# minimoog-filter.net
KiCad netlist of a schematic drawn in EAGLE
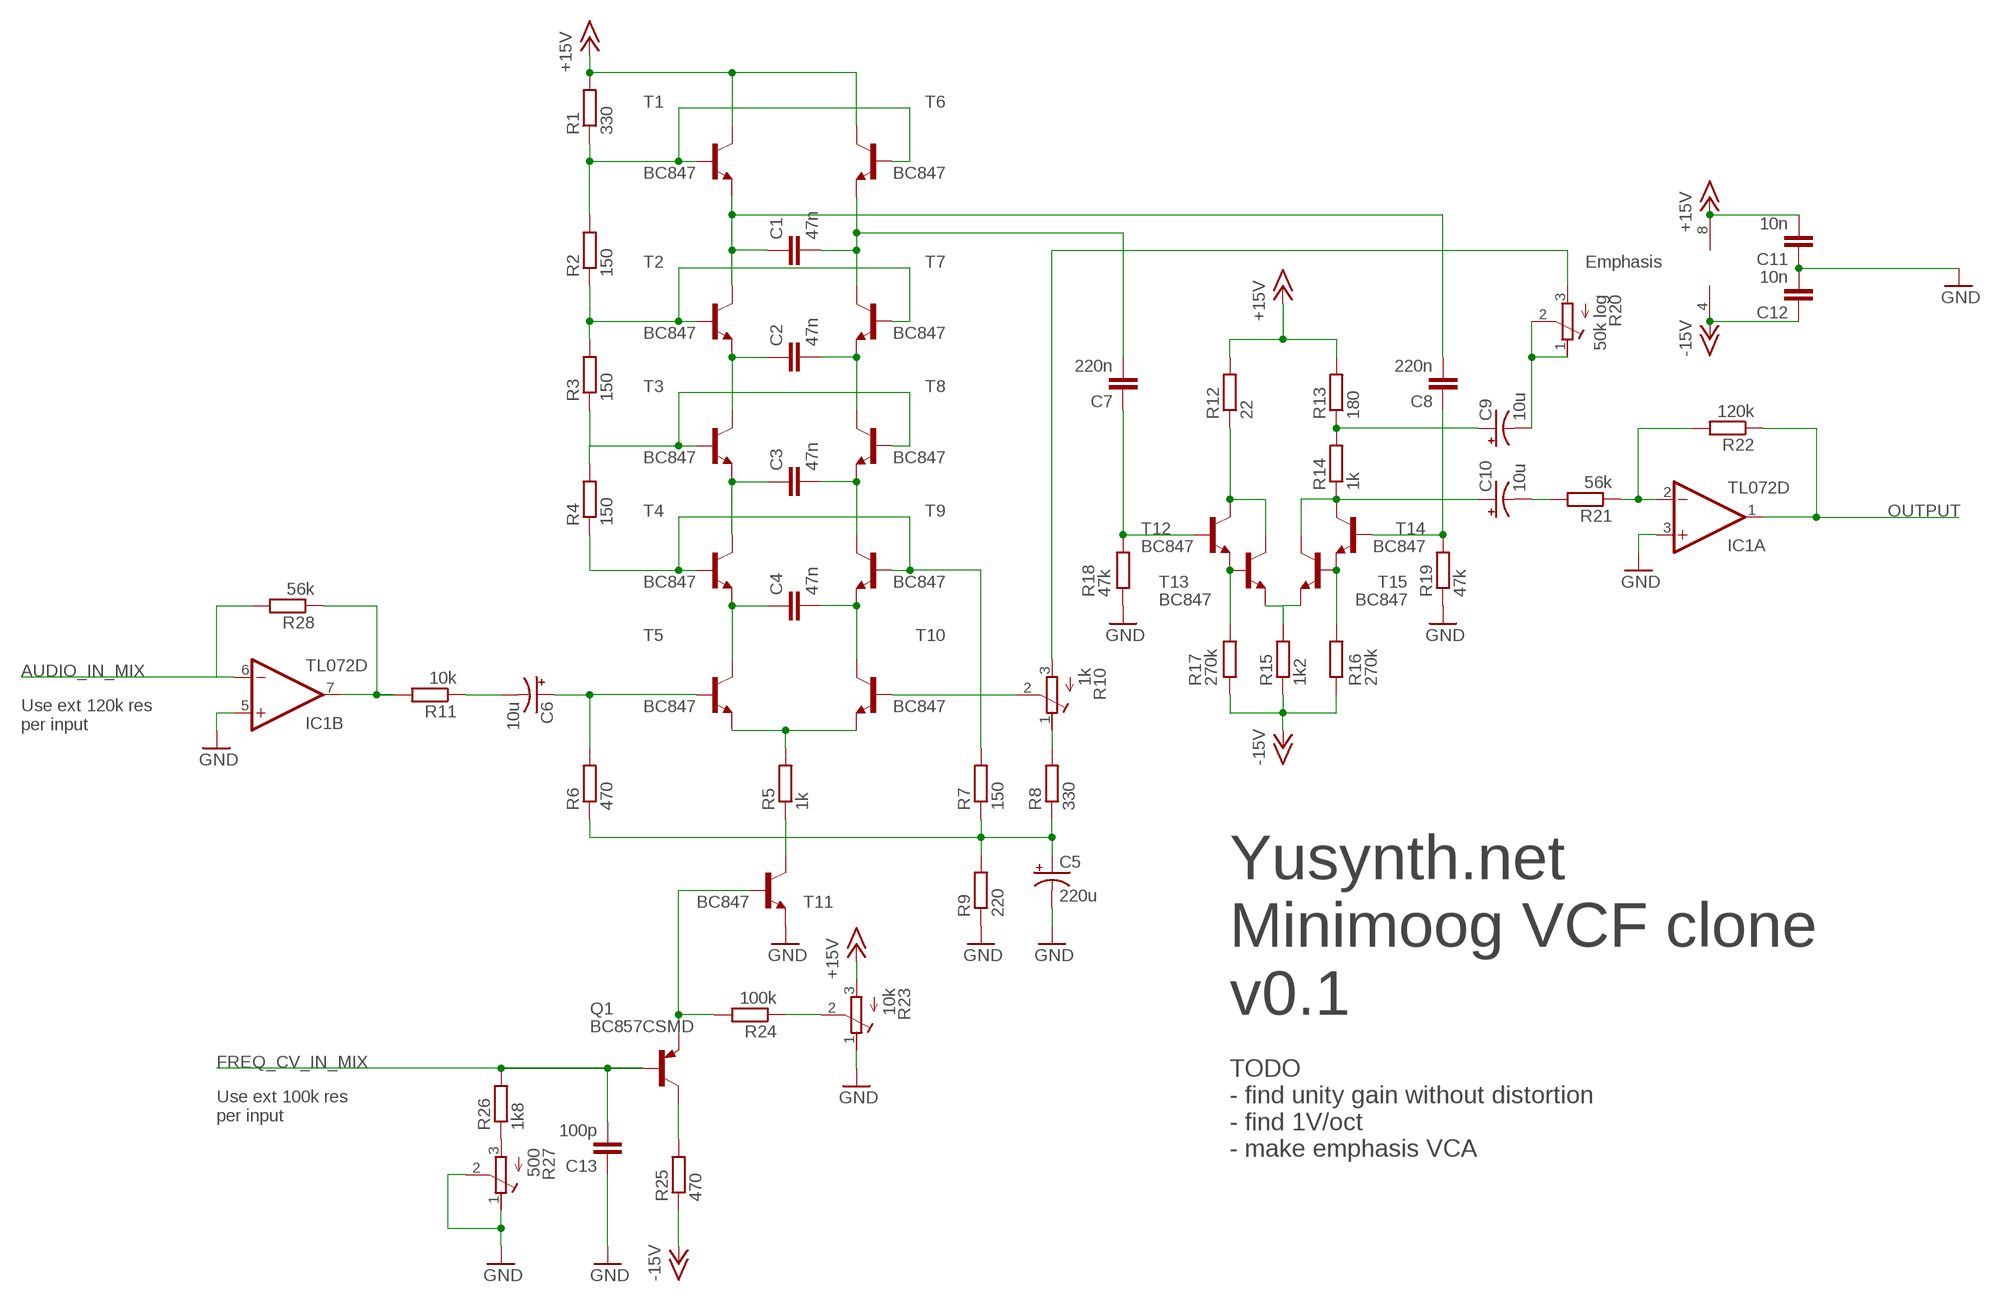
[diagram p0: schematic, sheet 1]

(export (version "E")
  (design (tool "Eeschema 10.0.6"))
  (components
    (comp (ref "C1")
      (value "47n")
      (footprint "eagle-import:C0805")
      (libsource (lib "eagle-import") (part "C-EUC0805"))
    )
    (comp (ref "C2")
      (value "47n")
      (footprint "eagle-import:C0805")
      (libsource (lib "eagle-import") (part "C-EUC0805"))
    )
    (comp (ref "C3")
      (value "47n")
      (footprint "eagle-import:C0805")
      (libsource (lib "eagle-import") (part "C-EUC0805"))
    )
    (comp (ref "C4")
      (value "47n")
      (footprint "eagle-import:C0805")
      (libsource (lib "eagle-import") (part "C-EUC0805"))
    )
    (comp (ref "C5")
      (value "220u")
      (footprint "eagle-import:E2-5")
      (libsource (lib "eagle-import") (part "CPOL-USE2-5"))
    )
    (comp (ref "C6")
      (value "10u")
      (footprint "eagle-import:E2-5")
      (libsource (lib "eagle-import") (part "CPOL-USE2-5"))
    )
    (comp (ref "C7")
      (value "220n")
      (footprint "eagle-import:C0805")
      (libsource (lib "eagle-import") (part "C-EUC0805"))
    )
    (comp (ref "C8")
      (value "220n")
      (footprint "eagle-import:C0805")
      (libsource (lib "eagle-import") (part "C-EUC0805"))
    )
    (comp (ref "C9")
      (value "10u")
      (footprint "eagle-import:E2-5")
      (libsource (lib "eagle-import") (part "CPOL-USE2-5"))
    )
    (comp (ref "C10")
      (value "10u")
      (footprint "eagle-import:E2-5")
      (libsource (lib "eagle-import") (part "CPOL-USE2-5"))
    )
    (comp (ref "C11")
      (value "10n")
      (footprint "eagle-import:C0805")
      (libsource (lib "eagle-import") (part "C-EUC0805"))
    )
    (comp (ref "C12")
      (value "10n")
      (footprint "eagle-import:C0805")
      (libsource (lib "eagle-import") (part "C-EUC0805"))
    )
    (comp (ref "C13")
      (value "100p")
      (footprint "eagle-import:C0805")
      (libsource (lib "eagle-import") (part "C-EUC0805"))
    )
    (comp (ref "IC1")
      (value "TL072D")
      (footprint "eagle-import:SO08")
      (libsource (lib "eagle-import") (part "TL072D"))
    )
    (comp (ref "Q1")
      (value "BC857CSMD")
      (footprint "eagle-import:SOT23-BEC")
      (libsource (lib "eagle-import") (part "BC857SMDC"))
    )
    (comp (ref "R1")
      (value "330")
      (footprint "eagle-import:R0805")
      (libsource (lib "eagle-import") (part "R-EU_R0805"))
    )
    (comp (ref "R2")
      (value "150")
      (footprint "eagle-import:R0805")
      (libsource (lib "eagle-import") (part "R-EU_R0805"))
    )
    (comp (ref "R3")
      (value "150")
      (footprint "eagle-import:R0805")
      (libsource (lib "eagle-import") (part "R-EU_R0805"))
    )
    (comp (ref "R4")
      (value "150")
      (footprint "eagle-import:R0805")
      (libsource (lib "eagle-import") (part "R-EU_R0805"))
    )
    (comp (ref "R5")
      (value "1k")
      (footprint "eagle-import:R0805")
      (libsource (lib "eagle-import") (part "R-EU_R0805"))
    )
    (comp (ref "R6")
      (value "470")
      (footprint "eagle-import:R0805")
      (libsource (lib "eagle-import") (part "R-EU_R0805"))
    )
    (comp (ref "R7")
      (value "150")
      (footprint "eagle-import:R0805")
      (libsource (lib "eagle-import") (part "R-EU_R0805"))
    )
    (comp (ref "R8")
      (value "330")
      (footprint "eagle-import:R0805")
      (libsource (lib "eagle-import") (part "R-EU_R0805"))
    )
    (comp (ref "R9")
      (value "220")
      (footprint "eagle-import:R0805")
      (libsource (lib "eagle-import") (part "R-EU_R0805"))
    )
    (comp (ref "R10")
      (value "1k")
      (footprint "eagle-import:RTRIMT93YA")
      (libsource (lib "eagle-import") (part "R-TRIMMT93YA"))
    )
    (comp (ref "R11")
      (value "10k")
      (footprint "eagle-import:R0805")
      (libsource (lib "eagle-import") (part "R-EU_R0805"))
    )
    (comp (ref "R12")
      (value "22")
      (footprint "eagle-import:R0805")
      (libsource (lib "eagle-import") (part "R-EU_R0805"))
    )
    (comp (ref "R13")
      (value "180")
      (footprint "eagle-import:R0805")
      (libsource (lib "eagle-import") (part "R-EU_R0805"))
    )
    (comp (ref "R14")
      (value "1k")
      (footprint "eagle-import:R0805")
      (libsource (lib "eagle-import") (part "R-EU_R0805"))
    )
    (comp (ref "R15")
      (value "1k2")
      (footprint "eagle-import:R0805")
      (libsource (lib "eagle-import") (part "R-EU_R0805"))
    )
    (comp (ref "R16")
      (value "270k")
      (footprint "eagle-import:R0805")
      (libsource (lib "eagle-import") (part "R-EU_R0805"))
    )
    (comp (ref "R17")
      (value "270k")
      (footprint "eagle-import:R0805")
      (libsource (lib "eagle-import") (part "R-EU_R0805"))
    )
    (comp (ref "R18")
      (value "47k")
      (footprint "eagle-import:R0805")
      (libsource (lib "eagle-import") (part "R-EU_R0805"))
    )
    (comp (ref "R19")
      (value "47k")
      (footprint "eagle-import:R0805")
      (libsource (lib "eagle-import") (part "R-EU_R0805"))
    )
    (comp (ref "R20")
      (value "50k log")
      (footprint "eagle-import:RTRIMT93YA")
      (libsource (lib "eagle-import") (part "R-TRIMMT93YA"))
    )
    (comp (ref "R21")
      (value "56k")
      (footprint "eagle-import:R0805")
      (libsource (lib "eagle-import") (part "R-EU_R0805"))
    )
    (comp (ref "R22")
      (value "120k")
      (footprint "eagle-import:R0805")
      (libsource (lib "eagle-import") (part "R-EU_R0805"))
    )
    (comp (ref "R23")
      (value "10k")
      (footprint "eagle-import:RTRIMT93YA")
      (libsource (lib "eagle-import") (part "R-TRIMMT93YA"))
    )
    (comp (ref "R24")
      (value "100k")
      (footprint "eagle-import:R0805")
      (libsource (lib "eagle-import") (part "R-EU_R0805"))
    )
    (comp (ref "R25")
      (value "470")
      (footprint "eagle-import:R0805")
      (libsource (lib "eagle-import") (part "R-EU_R0805"))
    )
    (comp (ref "R26")
      (value "1k8")
      (footprint "eagle-import:R0805")
      (libsource (lib "eagle-import") (part "R-EU_R0805"))
    )
    (comp (ref "R27")
      (value "500")
      (footprint "eagle-import:RTRIMT93YA")
      (libsource (lib "eagle-import") (part "R-TRIMMT93YA"))
    )
    (comp (ref "R28")
      (value "56k")
      (footprint "eagle-import:R0805")
      (libsource (lib "eagle-import") (part "R-EU_R0805"))
    )
    (comp (ref "T1")
      (value "BC847")
      (footprint "eagle-import:SOT23")
      (libsource (lib "eagle-import") (part "BC847"))
    )
    (comp (ref "T2")
      (value "BC847")
      (footprint "eagle-import:SOT23")
      (libsource (lib "eagle-import") (part "BC847"))
    )
    (comp (ref "T3")
      (value "BC847")
      (footprint "eagle-import:SOT23")
      (libsource (lib "eagle-import") (part "BC847"))
    )
    (comp (ref "T4")
      (value "BC847")
      (footprint "eagle-import:SOT23")
      (libsource (lib "eagle-import") (part "BC847"))
    )
    (comp (ref "T5")
      (value "BC847")
      (footprint "eagle-import:SOT23")
      (libsource (lib "eagle-import") (part "BC847"))
    )
    (comp (ref "T6")
      (value "BC847")
      (footprint "eagle-import:SOT23")
      (libsource (lib "eagle-import") (part "BC847"))
    )
    (comp (ref "T7")
      (value "BC847")
      (footprint "eagle-import:SOT23")
      (libsource (lib "eagle-import") (part "BC847"))
    )
    (comp (ref "T8")
      (value "BC847")
      (footprint "eagle-import:SOT23")
      (libsource (lib "eagle-import") (part "BC847"))
    )
    (comp (ref "T9")
      (value "BC847")
      (footprint "eagle-import:SOT23")
      (libsource (lib "eagle-import") (part "BC847"))
    )
    (comp (ref "T10")
      (value "BC847")
      (footprint "eagle-import:SOT23")
      (libsource (lib "eagle-import") (part "BC847"))
    )
    (comp (ref "T11")
      (value "BC847")
      (footprint "eagle-import:SOT23")
      (libsource (lib "eagle-import") (part "BC847"))
    )
    (comp (ref "T12")
      (value "BC847")
      (footprint "eagle-import:SOT23")
      (libsource (lib "eagle-import") (part "BC847"))
    )
    (comp (ref "T13")
      (value "BC847")
      (footprint "eagle-import:SOT23")
      (libsource (lib "eagle-import") (part "BC847"))
    )
    (comp (ref "T14")
      (value "BC847")
      (footprint "eagle-import:SOT23")
      (libsource (lib "eagle-import") (part "BC847"))
    )
    (comp (ref "T15")
      (value "BC847")
      (footprint "eagle-import:SOT23")
      (libsource (lib "eagle-import") (part "BC847"))
    )
  )
  (nets
    (net (code "1") (name "+15V") (class "Default")
      (node (ref "C11") (pin "2") (pinfunction "2_2") (pintype "passive"))
      (node (ref "IC1") (pin "8") (pinfunction "V+_8") (pintype "power_in"))
      (node (ref "R1") (pin "2") (pinfunction "2_2") (pintype "passive"))
      (node (ref "R12") (pin "2") (pinfunction "2_2") (pintype "passive"))
      (node (ref "R13") (pin "2") (pinfunction "2_2") (pintype "passive"))
      (node (ref "R23") (pin "3") (pinfunction "E_3") (pintype "passive"))
      (node (ref "T1") (pin "3") (pinfunction "C_3") (pintype "passive"))
      (node (ref "T6") (pin "3") (pinfunction "C_3") (pintype "passive"))
    )
    (net (code "2") (name "-15V") (class "Default")
      (node (ref "C12") (pin "1") (pinfunction "1_1") (pintype "passive"))
      (node (ref "IC1") (pin "4") (pinfunction "V-_4") (pintype "power_in"))
      (node (ref "R15") (pin "1") (pinfunction "1_1") (pintype "passive"))
      (node (ref "R16") (pin "1") (pinfunction "1_1") (pintype "passive"))
      (node (ref "R17") (pin "1") (pinfunction "1_1") (pintype "passive"))
      (node (ref "R25") (pin "1") (pinfunction "1_1") (pintype "passive"))
    )
    (net (code "3") (name "/AUDIO_IN_MIX") (class "Default")
      (node (ref "IC1") (pin "6") (pinfunction "-IN_6") (pintype "input"))
      (node (ref "R28") (pin "2") (pinfunction "2_2") (pintype "passive"))
    )
    (net (code "4") (name "/FREQ_CV_IN_MIX") (class "Default")
      (node (ref "C13") (pin "2") (pinfunction "2_2") (pintype "passive"))
      (node (ref "Q1") (pin "B") (pinfunction "B_B") (pintype "passive"))
      (node (ref "R26") (pin "2") (pinfunction "2_2") (pintype "passive"))
    )
    (net (code "5") (name "/OUTPUT") (class "Default")
      (node (ref "IC1") (pin "1") (pinfunction "OUT_1") (pintype "output"))
      (node (ref "R22") (pin "1") (pinfunction "1_1") (pintype "passive"))
    )
    (net (code "6") (name "GND") (class "Default")
      (node (ref "C11") (pin "1") (pinfunction "1_1") (pintype "passive"))
      (node (ref "C12") (pin "2") (pinfunction "2_2") (pintype "passive"))
      (node (ref "C13") (pin "1") (pinfunction "1_1") (pintype "passive"))
      (node (ref "C5") (pin "-") (pinfunction "-_-") (pintype "passive"))
      (node (ref "IC1") (pin "3") (pinfunction "+IN_3") (pintype "input"))
      (node (ref "IC1") (pin "5") (pinfunction "+IN_5") (pintype "input"))
      (node (ref "R18") (pin "1") (pinfunction "1_1") (pintype "passive"))
      (node (ref "R19") (pin "1") (pinfunction "1_1") (pintype "passive"))
      (node (ref "R23") (pin "1") (pinfunction "A_1") (pintype "passive"))
      (node (ref "R27") (pin "1") (pinfunction "A_1") (pintype "passive"))
      (node (ref "R27") (pin "2") (pinfunction "S_2") (pintype "passive"))
      (node (ref "R9") (pin "1") (pinfunction "1_1") (pintype "passive"))
      (node (ref "T11") (pin "2") (pinfunction "E_2") (pintype "passive"))
    )
    (net (code "7") (name "Net-(C5-Pad+)") (class "Default")
      (node (ref "C5") (pin "+") (pinfunction "+_+") (pintype "passive"))
      (node (ref "R6") (pin "1") (pinfunction "1_1") (pintype "passive"))
      (node (ref "R7") (pin "1") (pinfunction "1_1") (pintype "passive"))
      (node (ref "R8") (pin "1") (pinfunction "1_1") (pintype "passive"))
      (node (ref "R9") (pin "2") (pinfunction "2_2") (pintype "passive"))
    )
    (net (code "8") (name "Net-(C6-Pad-)") (class "Default")
      (node (ref "C6") (pin "-") (pinfunction "-_-") (pintype "passive"))
      (node (ref "R11") (pin "1") (pinfunction "1_1") (pintype "passive"))
    )
    (net (code "9") (name "Net-(C9-Pad+)") (class "Default")
      (node (ref "C9") (pin "+") (pinfunction "+_+") (pintype "passive"))
      (node (ref "R13") (pin "1") (pinfunction "1_1") (pintype "passive"))
      (node (ref "R14") (pin "2") (pinfunction "2_2") (pintype "passive"))
    )
    (net (code "10") (name "Net-(C10-Pad-)") (class "Default")
      (node (ref "C10") (pin "-") (pinfunction "-_-") (pintype "passive"))
      (node (ref "R21") (pin "2") (pinfunction "2_2") (pintype "passive"))
    )
    (net (code "11") (name "Net-(IC1A--IN)") (class "Default")
      (node (ref "IC1") (pin "2") (pinfunction "-IN_2") (pintype "input"))
      (node (ref "R21") (pin "1") (pinfunction "1_1") (pintype "passive"))
      (node (ref "R22") (pin "2") (pinfunction "2_2") (pintype "passive"))
    )
    (net (code "12") (name "Net-(IC1B-OUT)") (class "Default")
      (node (ref "IC1") (pin "7") (pinfunction "OUT_7") (pintype "output"))
      (node (ref "R11") (pin "2") (pinfunction "2_2") (pintype "passive"))
      (node (ref "R28") (pin "1") (pinfunction "1_1") (pintype "passive"))
    )
    (net (code "13") (name "Net-(Q1-PadC)") (class "Default")
      (node (ref "Q1") (pin "C") (pinfunction "C_C") (pintype "passive"))
      (node (ref "R25") (pin "2") (pinfunction "2_2") (pintype "passive"))
    )
    (net (code "14") (name "Net-(R10-A)") (class "Default")
      (node (ref "R10") (pin "1") (pinfunction "A_1") (pintype "passive"))
      (node (ref "R8") (pin "2") (pinfunction "2_2") (pintype "passive"))
    )
    (net (code "15") (name "Net-(R10-E)") (class "Default")
      (node (ref "R10") (pin "3") (pinfunction "E_3") (pintype "passive"))
      (node (ref "R20") (pin "3") (pinfunction "E_3") (pintype "passive"))
    )
    (net (code "16") (name "Net-(R10-S)") (class "Default")
      (node (ref "R10") (pin "2") (pinfunction "S_2") (pintype "passive"))
      (node (ref "T10") (pin "1") (pinfunction "B_1") (pintype "passive"))
    )
    (net (code "17") (name "Net-(R20-A)") (class "Default")
      (node (ref "C9") (pin "-") (pinfunction "-_-") (pintype "passive"))
      (node (ref "R20") (pin "1") (pinfunction "A_1") (pintype "passive"))
      (node (ref "R20") (pin "2") (pinfunction "S_2") (pintype "passive"))
    )
    (net (code "18") (name "Net-(R23-S)") (class "Default")
      (node (ref "R23") (pin "2") (pinfunction "S_2") (pintype "passive"))
      (node (ref "R24") (pin "1") (pinfunction "1_1") (pintype "passive"))
    )
    (net (code "19") (name "Net-(R27-E)") (class "Default")
      (node (ref "R26") (pin "1") (pinfunction "1_1") (pintype "passive"))
      (node (ref "R27") (pin "3") (pinfunction "E_3") (pintype "passive"))
    )
    (net (code "20") (name "Net-(T1-B)") (class "Default")
      (node (ref "R1") (pin "1") (pinfunction "1_1") (pintype "passive"))
      (node (ref "R2") (pin "2") (pinfunction "2_2") (pintype "passive"))
      (node (ref "T1") (pin "1") (pinfunction "B_1") (pintype "passive"))
      (node (ref "T6") (pin "1") (pinfunction "B_1") (pintype "passive"))
    )
    (net (code "21") (name "Net-(T1-E)") (class "Default")
      (node (ref "C1") (pin "1") (pinfunction "1_1") (pintype "passive"))
      (node (ref "C8") (pin "2") (pinfunction "2_2") (pintype "passive"))
      (node (ref "T1") (pin "2") (pinfunction "E_2") (pintype "passive"))
      (node (ref "T2") (pin "3") (pinfunction "C_3") (pintype "passive"))
    )
    (net (code "22") (name "Net-(T2-B)") (class "Default")
      (node (ref "R2") (pin "1") (pinfunction "1_1") (pintype "passive"))
      (node (ref "R3") (pin "2") (pinfunction "2_2") (pintype "passive"))
      (node (ref "T2") (pin "1") (pinfunction "B_1") (pintype "passive"))
      (node (ref "T7") (pin "1") (pinfunction "B_1") (pintype "passive"))
    )
    (net (code "23") (name "Net-(T2-E)") (class "Default")
      (node (ref "C2") (pin "1") (pinfunction "1_1") (pintype "passive"))
      (node (ref "T2") (pin "2") (pinfunction "E_2") (pintype "passive"))
      (node (ref "T3") (pin "3") (pinfunction "C_3") (pintype "passive"))
    )
    (net (code "24") (name "Net-(T3-B)") (class "Default")
      (node (ref "R3") (pin "1") (pinfunction "1_1") (pintype "passive"))
      (node (ref "R4") (pin "2") (pinfunction "2_2") (pintype "passive"))
      (node (ref "T3") (pin "1") (pinfunction "B_1") (pintype "passive"))
      (node (ref "T8") (pin "1") (pinfunction "B_1") (pintype "passive"))
    )
    (net (code "25") (name "Net-(T3-E)") (class "Default")
      (node (ref "C3") (pin "1") (pinfunction "1_1") (pintype "passive"))
      (node (ref "T3") (pin "2") (pinfunction "E_2") (pintype "passive"))
      (node (ref "T4") (pin "3") (pinfunction "C_3") (pintype "passive"))
    )
    (net (code "26") (name "Net-(T4-B)") (class "Default")
      (node (ref "R4") (pin "1") (pinfunction "1_1") (pintype "passive"))
      (node (ref "R7") (pin "2") (pinfunction "2_2") (pintype "passive"))
      (node (ref "T4") (pin "1") (pinfunction "B_1") (pintype "passive"))
      (node (ref "T9") (pin "1") (pinfunction "B_1") (pintype "passive"))
    )
    (net (code "27") (name "Net-(T4-E)") (class "Default")
      (node (ref "C4") (pin "1") (pinfunction "1_1") (pintype "passive"))
      (node (ref "T4") (pin "2") (pinfunction "E_2") (pintype "passive"))
      (node (ref "T5") (pin "3") (pinfunction "C_3") (pintype "passive"))
    )
    (net (code "28") (name "Net-(T5-B)") (class "Default")
      (node (ref "C6") (pin "+") (pinfunction "+_+") (pintype "passive"))
      (node (ref "R6") (pin "2") (pinfunction "2_2") (pintype "passive"))
      (node (ref "T5") (pin "1") (pinfunction "B_1") (pintype "passive"))
    )
    (net (code "29") (name "Net-(T6-E)") (class "Default")
      (node (ref "C1") (pin "2") (pinfunction "2_2") (pintype "passive"))
      (node (ref "C7") (pin "2") (pinfunction "2_2") (pintype "passive"))
      (node (ref "T6") (pin "2") (pinfunction "E_2") (pintype "passive"))
      (node (ref "T7") (pin "3") (pinfunction "C_3") (pintype "passive"))
    )
    (net (code "30") (name "Net-(T7-E)") (class "Default")
      (node (ref "C2") (pin "2") (pinfunction "2_2") (pintype "passive"))
      (node (ref "T7") (pin "2") (pinfunction "E_2") (pintype "passive"))
      (node (ref "T8") (pin "3") (pinfunction "C_3") (pintype "passive"))
    )
    (net (code "31") (name "Net-(T8-E)") (class "Default")
      (node (ref "C3") (pin "2") (pinfunction "2_2") (pintype "passive"))
      (node (ref "T8") (pin "2") (pinfunction "E_2") (pintype "passive"))
      (node (ref "T9") (pin "3") (pinfunction "C_3") (pintype "passive"))
    )
    (net (code "32") (name "Net-(T10-C)") (class "Default")
      (node (ref "C4") (pin "2") (pinfunction "2_2") (pintype "passive"))
      (node (ref "T10") (pin "3") (pinfunction "C_3") (pintype "passive"))
      (node (ref "T9") (pin "2") (pinfunction "E_2") (pintype "passive"))
    )
    (net (code "33") (name "Net-(T10-E)") (class "Default")
      (node (ref "R5") (pin "2") (pinfunction "2_2") (pintype "passive"))
      (node (ref "T10") (pin "2") (pinfunction "E_2") (pintype "passive"))
      (node (ref "T5") (pin "2") (pinfunction "E_2") (pintype "passive"))
    )
    (net (code "34") (name "Net-(T11-B)") (class "Default")
      (node (ref "Q1") (pin "E") (pinfunction "E_E") (pintype "passive"))
      (node (ref "R24") (pin "2") (pinfunction "2_2") (pintype "passive"))
      (node (ref "T11") (pin "1") (pinfunction "B_1") (pintype "passive"))
    )
    (net (code "35") (name "Net-(T11-C)") (class "Default")
      (node (ref "R5") (pin "1") (pinfunction "1_1") (pintype "passive"))
      (node (ref "T11") (pin "3") (pinfunction "C_3") (pintype "passive"))
    )
    (net (code "36") (name "Net-(T12-B)") (class "Default")
      (node (ref "C7") (pin "1") (pinfunction "1_1") (pintype "passive"))
      (node (ref "R18") (pin "2") (pinfunction "2_2") (pintype "passive"))
      (node (ref "T12") (pin "1") (pinfunction "B_1") (pintype "passive"))
    )
    (net (code "37") (name "Net-(T12-C)") (class "Default")
      (node (ref "R12") (pin "1") (pinfunction "1_1") (pintype "passive"))
      (node (ref "T12") (pin "3") (pinfunction "C_3") (pintype "passive"))
      (node (ref "T13") (pin "3") (pinfunction "C_3") (pintype "passive"))
    )
    (net (code "38") (name "Net-(T12-E)") (class "Default")
      (node (ref "R17") (pin "2") (pinfunction "2_2") (pintype "passive"))
      (node (ref "T12") (pin "2") (pinfunction "E_2") (pintype "passive"))
      (node (ref "T13") (pin "1") (pinfunction "B_1") (pintype "passive"))
    )
    (net (code "39") (name "Net-(T13-E)") (class "Default")
      (node (ref "R15") (pin "2") (pinfunction "2_2") (pintype "passive"))
      (node (ref "T13") (pin "2") (pinfunction "E_2") (pintype "passive"))
      (node (ref "T15") (pin "2") (pinfunction "E_2") (pintype "passive"))
    )
    (net (code "40") (name "Net-(T14-B)") (class "Default")
      (node (ref "C8") (pin "1") (pinfunction "1_1") (pintype "passive"))
      (node (ref "R19") (pin "2") (pinfunction "2_2") (pintype "passive"))
      (node (ref "T14") (pin "1") (pinfunction "B_1") (pintype "passive"))
    )
    (net (code "41") (name "Net-(T14-C)") (class "Default")
      (node (ref "C10") (pin "+") (pinfunction "+_+") (pintype "passive"))
      (node (ref "R14") (pin "1") (pinfunction "1_1") (pintype "passive"))
      (node (ref "T14") (pin "3") (pinfunction "C_3") (pintype "passive"))
      (node (ref "T15") (pin "3") (pinfunction "C_3") (pintype "passive"))
    )
    (net (code "42") (name "Net-(T14-E)") (class "Default")
      (node (ref "R16") (pin "2") (pinfunction "2_2") (pintype "passive"))
      (node (ref "T14") (pin "2") (pinfunction "E_2") (pintype "passive"))
      (node (ref "T15") (pin "1") (pinfunction "B_1") (pintype "passive"))
    )
  )
)
